# SCH_BusinessCard_2024-06-08.net
KiCad netlist of a schematic drawn in EasyEDA
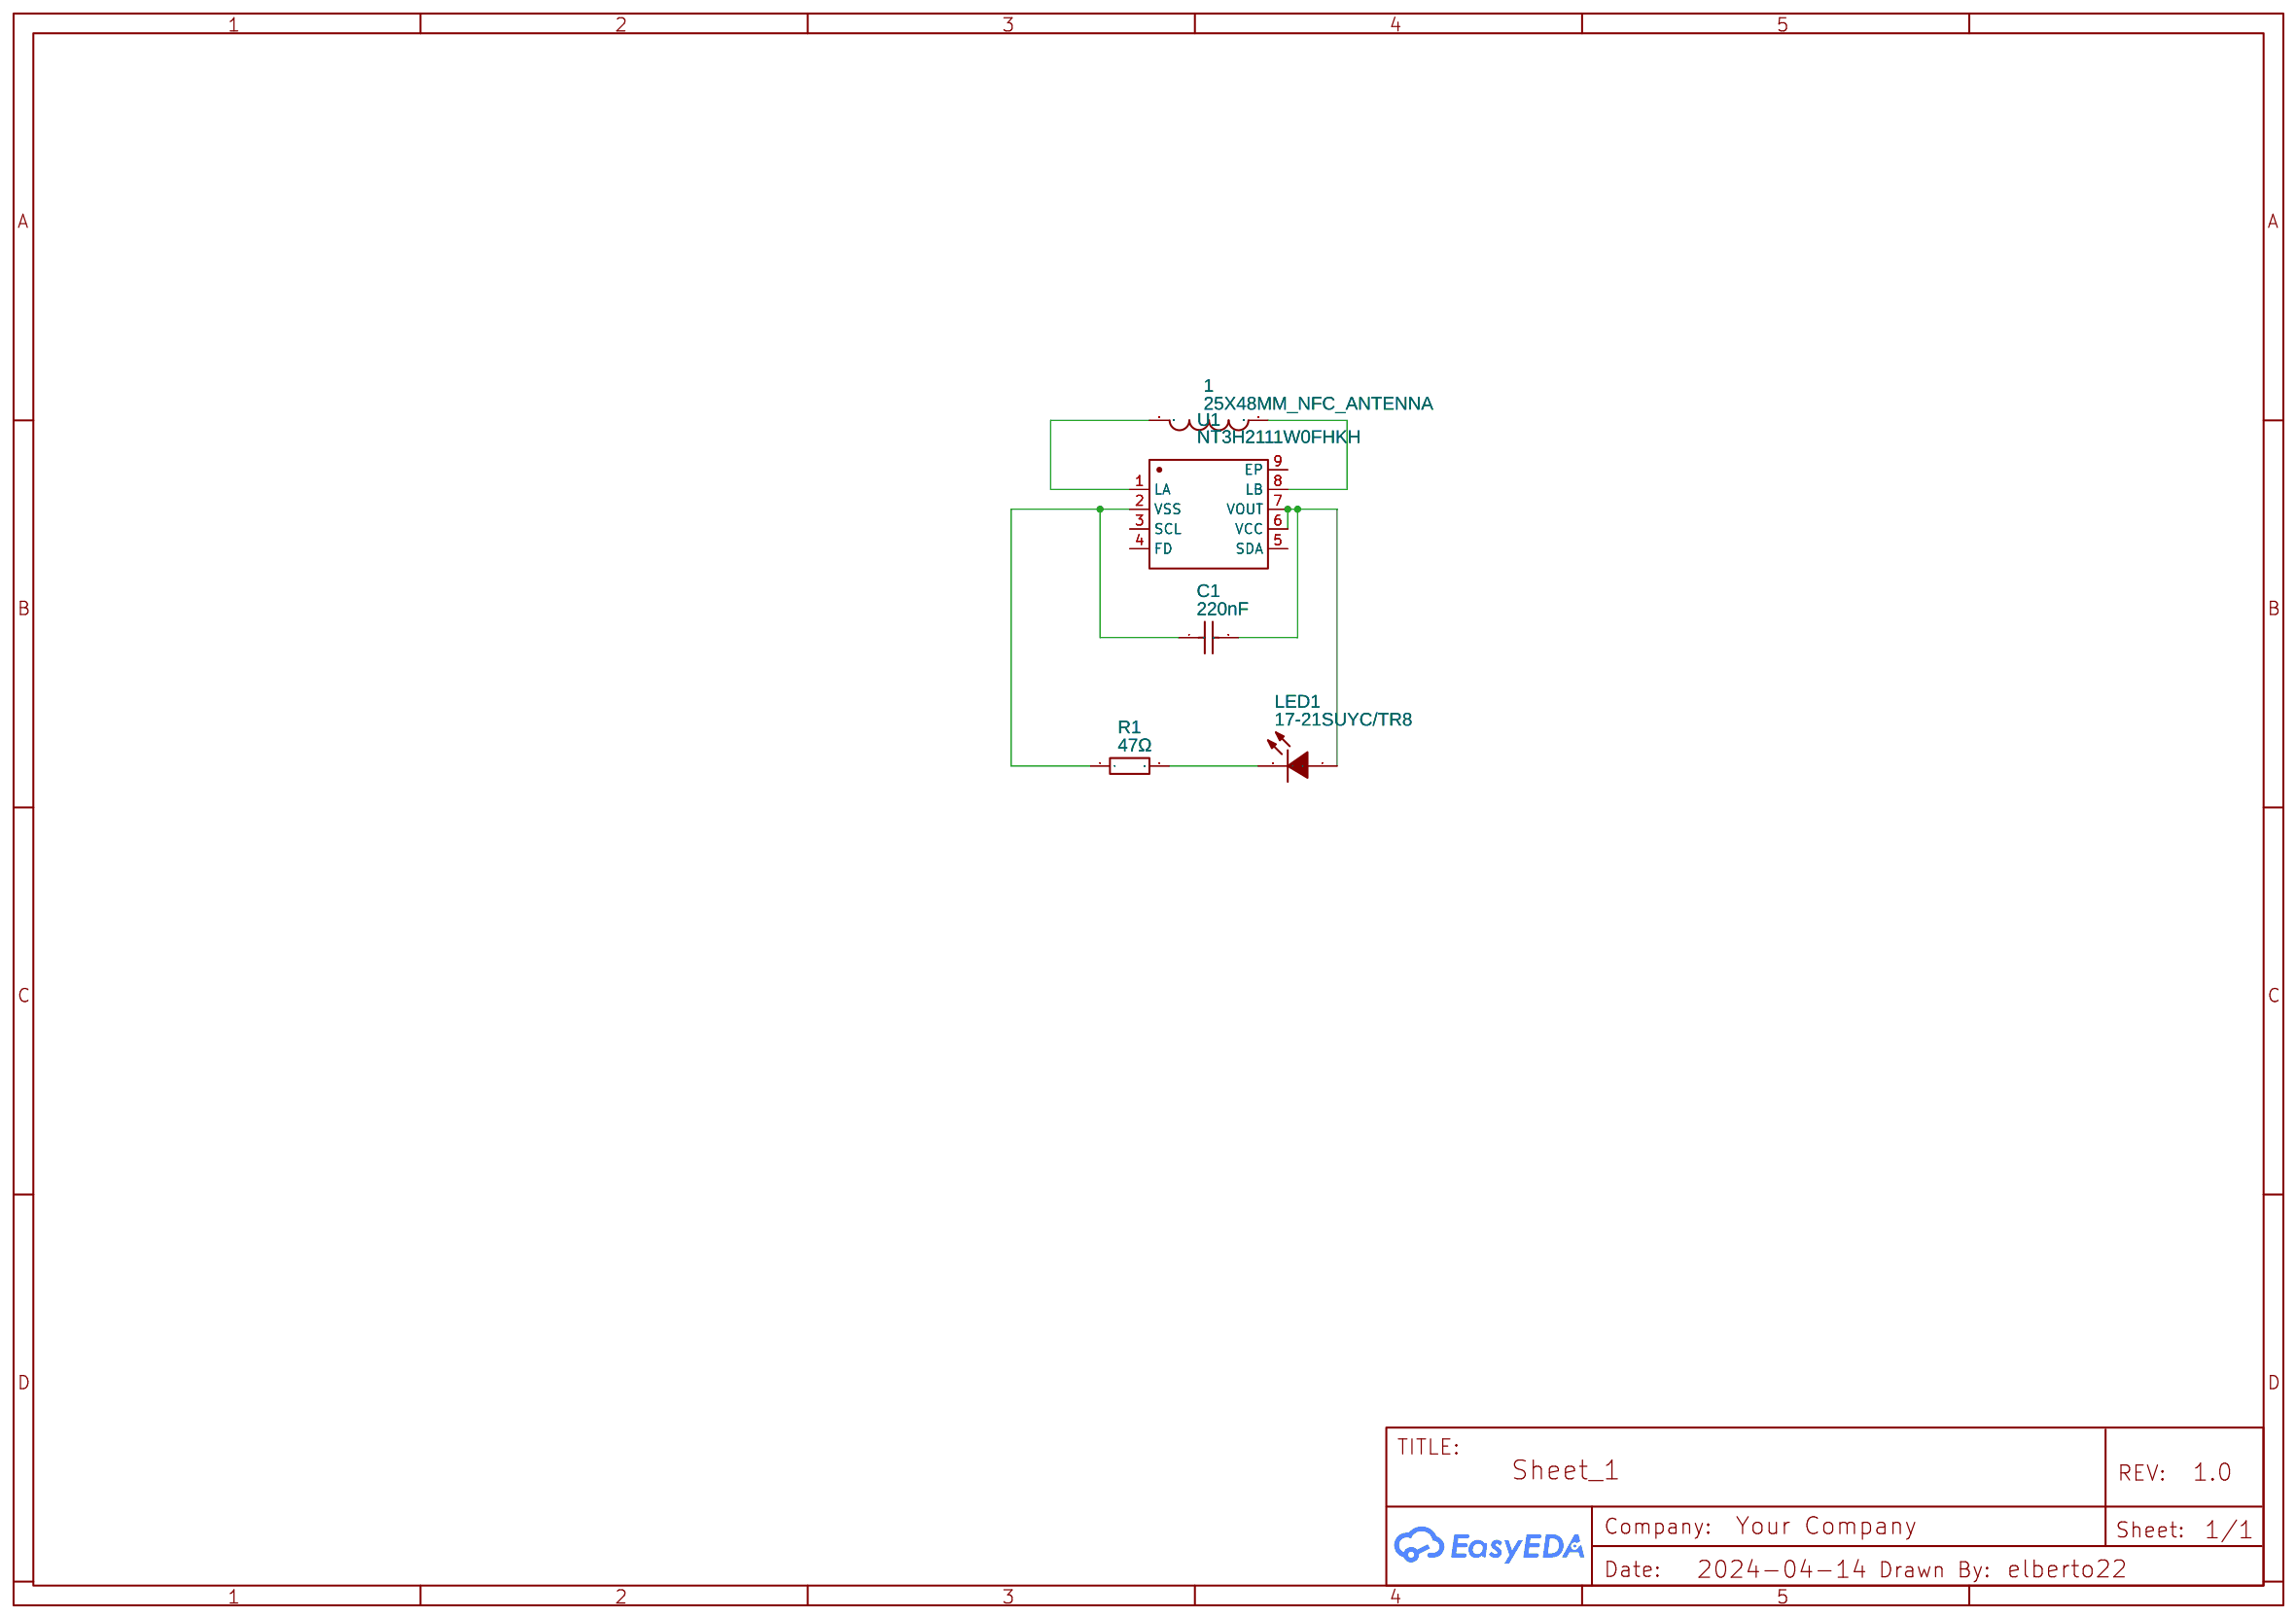
[diagram p0: schematic sheet]

(export (version "E")
  (design (tool "Eeschema 10.0.6"))
  (components
    (comp (ref "1") (value "25X48MM_NFC_ANTENNA") (libsource (lib "") (part "25X48MM_NFC_ANTENNA")))
    (comp (ref "C1")
      (value "220nF")
      (fields
        (field (name "Manufacturer Part") "CL10B224KA8NNNC")
        (field (name "Manufacturer") "SAMSUNG(三星)")
      )
      (libsource (lib "") (part "CL10B224KA8NNNC"))
    )
    (comp (ref "LED1")
      (value "17-21SUYC/TR8")
      (fields (field (name "Manufacturer Part") "KT-0805黄灯") (field (name "Manufacturer") "KENTO"))
      (libsource (lib "") (part "17-21SUYC/TR8"))
    )
    (comp (ref "R1")
      (value "47Ω")
      (fields
        (field (name "Manufacturer Part") "0603WAF470JT5E")
        (field (name "Manufacturer") "UNI-ROYAL(厚声)")
      )
      (libsource (lib "") (part "0603WAF470JT5E"))
    )
    (comp (ref "U1")
      (value "NT3H2111W0FHKH")
      (fields (field (name "Manufacturer") "NXP(恩智浦)"))
      (libsource (lib "") (part "NT3H2111W0FHKH"))
    )
  )
  (nets
    (net (code "1") (name "Net-(LED1-+)") (class "Default")
      (node (ref "C1") (pin "2") (pinfunction "2_2") (pintype "input"))
      (node (ref "LED1") (pin "1") (pinfunction "+_1") (pintype "unspecified"))
      (node (ref "U1") (pin "6") (pinfunction "VCC_6") (pintype "unspecified"))
      (node (ref "U1") (pin "7") (pinfunction "VOUT_7") (pintype "unspecified"))
    )
    (net (code "2") (name "Net-(LED1--)") (class "Default")
      (node (ref "LED1") (pin "2") (pinfunction "-_2") (pintype "unspecified"))
      (node (ref "R1") (pin "2") (pinfunction "2_2") (pintype "input"))
    )
    (net (code "3") (name "Net-(U1-LA)") (class "Default")
      (node (ref "1") (pin "P$2") (pinfunction "P$2_P$2") (pintype "bidirectional"))
      (node (ref "U1") (pin "1") (pinfunction "LA_1") (pintype "unspecified"))
    )
    (net (code "4") (name "Net-(U1-LB)") (class "Default")
      (node (ref "1") (pin "P$1") (pinfunction "P$1_P$1") (pintype "bidirectional"))
      (node (ref "U1") (pin "8") (pinfunction "LB_8") (pintype "unspecified"))
    )
    (net (code "5") (name "Net-(U1-VSS)") (class "Default")
      (node (ref "C1") (pin "1") (pinfunction "1_1") (pintype "input"))
      (node (ref "R1") (pin "1") (pinfunction "1_1") (pintype "input"))
      (node (ref "U1") (pin "2") (pinfunction "VSS_2") (pintype "unspecified"))
    )
    (net (code "6") (name "unconnected-(U1-EP-Pad9)") (class "Default")
      (node (ref "U1") (pin "9") (pinfunction "EP_9") (pintype "unspecified"))
    )
    (net (code "7") (name "unconnected-(U1-FD-Pad4)") (class "Default")
      (node (ref "U1") (pin "4") (pinfunction "FD_4") (pintype "unspecified"))
    )
    (net (code "8") (name "unconnected-(U1-SCL-Pad3)") (class "Default")
      (node (ref "U1") (pin "3") (pinfunction "SCL_3") (pintype "unspecified"))
    )
    (net (code "9") (name "unconnected-(U1-SDA-Pad5)") (class "Default")
      (node (ref "U1") (pin "5") (pinfunction "SDA_5") (pintype "unspecified"))
    )
  )
)
